# DWM3000_Anchor.net
KiCad netlist of a schematic drawn in Altium Designer
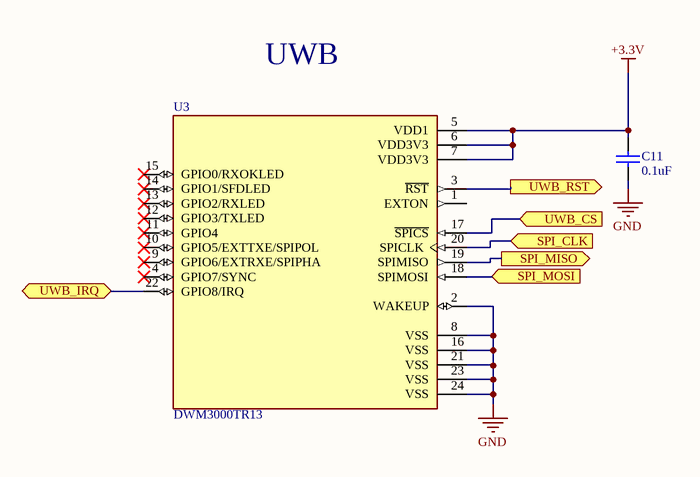
[diagram p0: DWM3000_Anchor.SchDoc]

(export (version "E")
  (design (tool "Eeschema 10.0.6"))
  (components
    (comp (ref "C11")
      (value "0.1uF")
      (footprint "CAPC1005X55N")
      (description "Capacitor")
      (fields (field (name "Comment") "Cap") (field (name "PUBLISHER") "Altium Limited"))
      (libsource (lib "Miscellaneous Devices") (part "Cap"))
    )
    (comp (ref "U3")
      (value "DWM3000TR13")
      (footprint "XCVR_DWM3000TR13")
      (fields (field (name "MF") "Qorvo"))
      (libsource (lib "DWM3000TR13") (part "DWM3000TR13"))
    )
  )
  (nets
    (net (code "1") (name "+3.3V") (class "Default")
      (node (ref "C11") (pin "2") (pinfunction "2_2") (pintype "passive"))
      (node (ref "U3") (pin "5") (pinfunction "VDD1_5") (pintype "power_in"))
      (node (ref "U3") (pin "6") (pinfunction "VDD3V3_6") (pintype "power_in"))
      (node (ref "U3") (pin "7") (pinfunction "VDD3V3_7") (pintype "power_in"))
    )
    (net (code "2") (name "/SPI_CLK") (class "Default")
      (node (ref "U3") (pin "20") (pinfunction "SPICLK_20") (pintype "input"))
    )
    (net (code "3") (name "/SPI_MISO") (class "Default")
      (node (ref "U3") (pin "19") (pinfunction "SPIMISO_19") (pintype "output"))
    )
    (net (code "4") (name "/SPI_MOSI") (class "Default")
      (node (ref "U3") (pin "18") (pinfunction "SPIMOSI_18") (pintype "input"))
    )
    (net (code "5") (name "/UWB_CS") (class "Default")
      (node (ref "U3") (pin "17") (pinfunction "~{SPICS}_17") (pintype "input"))
    )
    (net (code "6") (name "/UWB_IRQ") (class "Default")
      (node (ref "U3") (pin "22") (pinfunction "GPIO8/IRQ_22") (pintype "bidirectional"))
    )
    (net (code "7") (name "/UWB_RST") (class "Default")
      (node (ref "U3") (pin "3") (pinfunction "~{RST}_3") (pintype "output"))
    )
    (net (code "8") (name "GND") (class "Default")
      (node (ref "C11") (pin "1") (pinfunction "1_1") (pintype "passive"))
      (node (ref "U3") (pin "16") (pinfunction "VSS_16") (pintype "power_in"))
      (node (ref "U3") (pin "2") (pinfunction "WAKEUP_2") (pintype "bidirectional"))
      (node (ref "U3") (pin "21") (pinfunction "VSS_21") (pintype "power_in"))
      (node (ref "U3") (pin "23") (pinfunction "VSS_23") (pintype "power_in"))
      (node (ref "U3") (pin "24") (pinfunction "VSS_24") (pintype "power_in"))
      (node (ref "U3") (pin "8") (pinfunction "VSS_8") (pintype "power_in"))
    )
    (net (code "9") (name "unconnected-(U3-EXTON-Pad1)") (class "Default")
      (node (ref "U3") (pin "1") (pinfunction "EXTON_1") (pintype "output"))
    )
    (net (code "10") (name "unconnected-(U3-GPIO0{slash}RXOKLED-Pad15)") (class "Default")
      (node (ref "U3") (pin "15") (pinfunction "GPIO0/RXOKLED_15") (pintype "bidirectional+no_connect"))
    )
    (net (code "11") (name "unconnected-(U3-GPIO1{slash}SFDLED-Pad14)") (class "Default")
      (node (ref "U3") (pin "14") (pinfunction "GPIO1/SFDLED_14") (pintype "bidirectional+no_connect"))
    )
    (net (code "12") (name "unconnected-(U3-GPIO2{slash}RXLED-Pad13)") (class "Default")
      (node (ref "U3") (pin "13") (pinfunction "GPIO2/RXLED_13") (pintype "bidirectional+no_connect"))
    )
    (net (code "13") (name "unconnected-(U3-GPIO3{slash}TXLED-Pad12)") (class "Default")
      (node (ref "U3") (pin "12") (pinfunction "GPIO3/TXLED_12") (pintype "bidirectional+no_connect"))
    )
    (net (code "14") (name "unconnected-(U3-GPIO4-Pad11)") (class "Default")
      (node (ref "U3") (pin "11") (pinfunction "GPIO4_11") (pintype "bidirectional+no_connect"))
    )
    (net (code "15") (name "unconnected-(U3-GPIO5{slash}EXTTXE{slash}SPIPOL-Pad10)") (class "Default")
      (node (ref "U3") (pin "10") (pinfunction "GPIO5/EXTTXE/SPIPOL_10") (pintype "bidirectional+no_connect"))
    )
    (net (code "16") (name "unconnected-(U3-GPIO6{slash}EXTRXE{slash}SPIPHA-Pad9)") (class "Default")
      (node (ref "U3") (pin "9") (pinfunction "GPIO6/EXTRXE/SPIPHA_9") (pintype "bidirectional+no_connect"))
    )
    (net (code "17") (name "unconnected-(U3-GPIO7{slash}SYNC-Pad4)") (class "Default")
      (node (ref "U3") (pin "4") (pinfunction "GPIO7/SYNC_4") (pintype "bidirectional+no_connect"))
    )
  )
)
